# Schaltplan.net
KiCad netlist of a schematic drawn in EAGLE
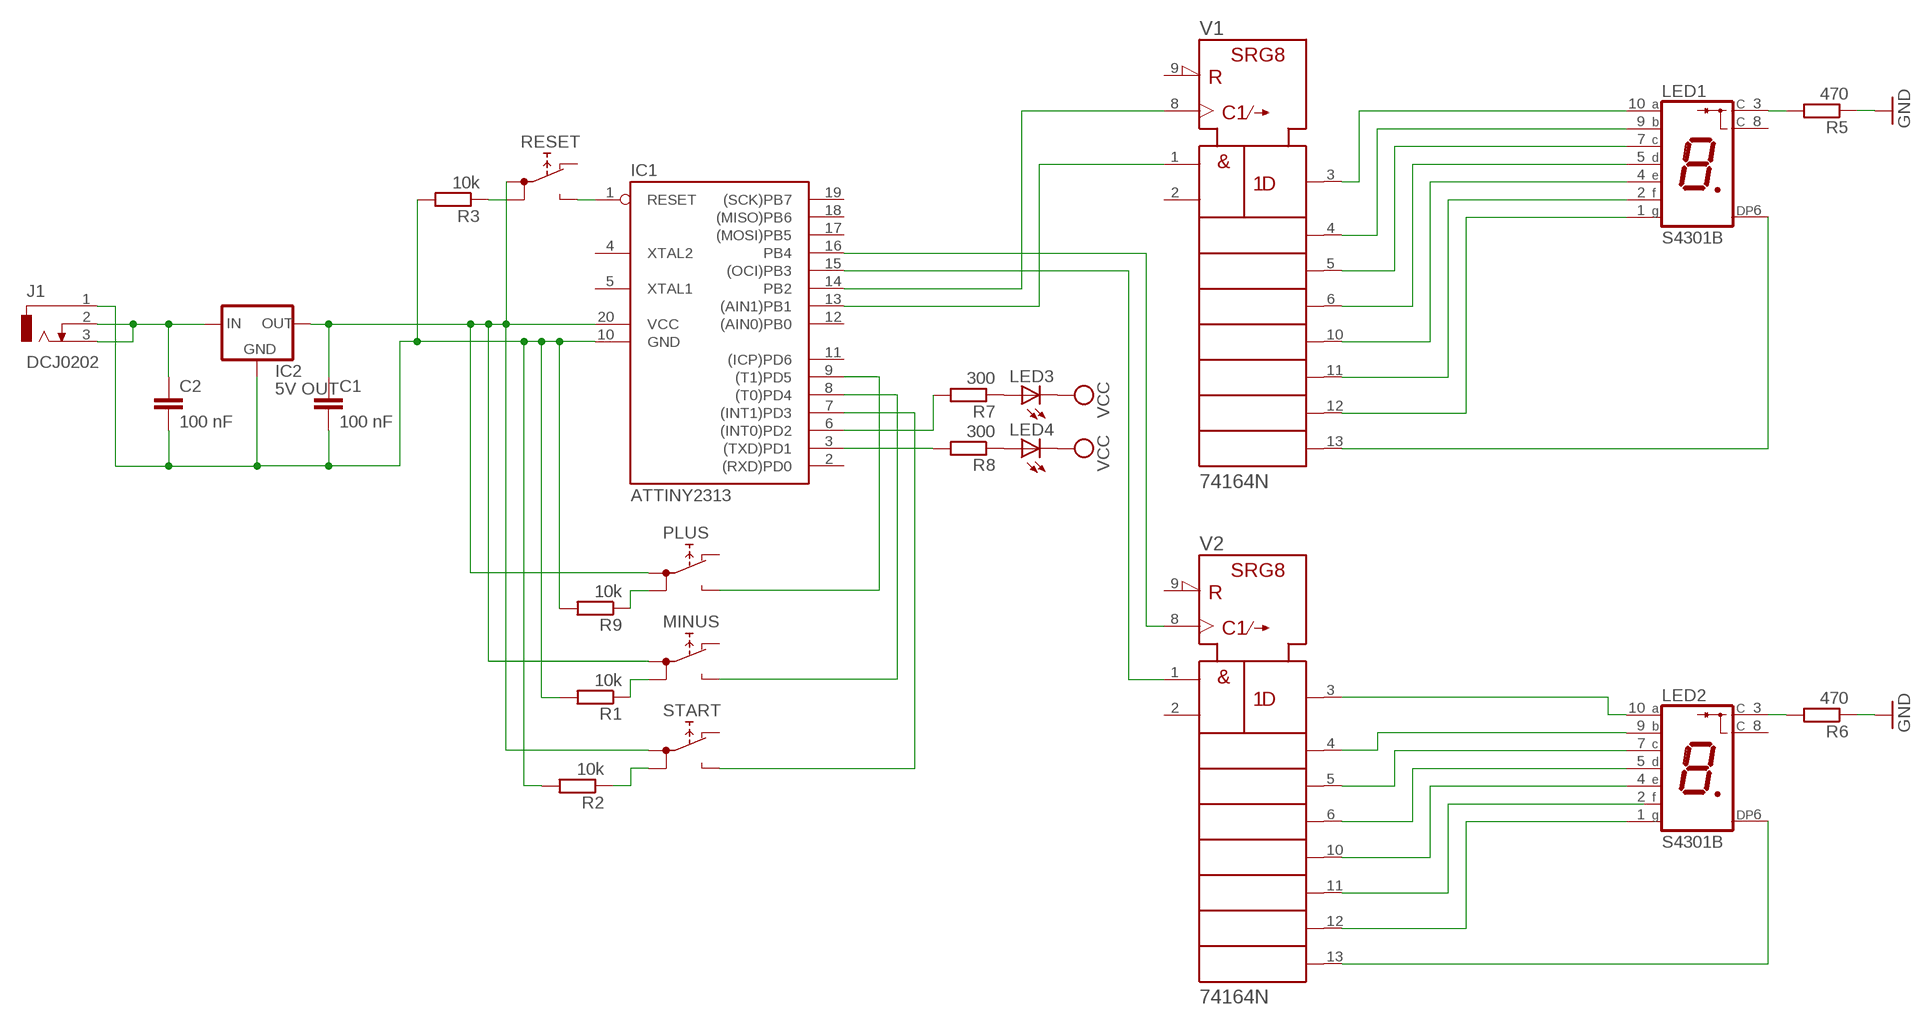
[diagram p0: schematic, sheet 1]

(export (version "E")
  (design (tool "Eeschema 10.0.6"))
  (components
    (comp (ref "C1")
      (value "100 nF")
      (footprint "eagle-import:C025-024X044")
      (libsource (lib "eagle-import") (part "C-EU025-024X044"))
    )
    (comp (ref "C2")
      (value "100 nF")
      (footprint "eagle-import:C025-024X044")
      (libsource (lib "eagle-import") (part "C-EU025-024X044"))
    )
    (comp (ref "IC1")
      (value "ATTINY2313")
      (footprint "eagle-import:DIL20")
      (libsource (lib "eagle-import") (part "AT90S2313P"))
    )
    (comp (ref "IC2")
      (value "5V OUT")
      (footprint "eagle-import:78MXXL")
      (libsource (lib "eagle-import") (part "78MXXL"))
    )
    (comp (ref "J1")
      (value "DCJ0202")
      (footprint "eagle-import:DCJ0202")
      (libsource (lib "eagle-import") (part "DCJ0202"))
    )
    (comp (ref "LED1")
      (value "S4301B")
      (footprint "eagle-import:S4301B")
      (libsource (lib "eagle-import") (part "S4301B"))
    )
    (comp (ref "LED2")
      (value "S4301B")
      (footprint "eagle-import:S4301B")
      (libsource (lib "eagle-import") (part "S4301B"))
    )
    (comp (ref "LED3")
      (value "LED3MM")
      (footprint "eagle-import:LED3MM")
      (libsource (lib "eagle-import") (part "LED3MM"))
    )
    (comp (ref "LED4")
      (value "LED3MM")
      (footprint "eagle-import:LED3MM")
      (libsource (lib "eagle-import") (part "LED3MM"))
    )
    (comp (ref "MINUS")
      (value "5501")
      (footprint "eagle-import:5501")
      (libsource (lib "eagle-import") (part "55?01"))
    )
    (comp (ref "PLUS")
      (value "5501")
      (footprint "eagle-import:5501")
      (libsource (lib "eagle-import") (part "55?01"))
    )
    (comp (ref "R1")
      (value "10k")
      (footprint "eagle-import:0204_7")
      (libsource (lib "eagle-import") (part "R-EU_0204/7"))
    )
    (comp (ref "R2")
      (value "10k")
      (footprint "eagle-import:0204_7")
      (libsource (lib "eagle-import") (part "R-EU_0204/7"))
    )
    (comp (ref "R3")
      (value "10k")
      (footprint "eagle-import:0204_7")
      (libsource (lib "eagle-import") (part "R-EU_0204/7"))
    )
    (comp (ref "R5")
      (value "470")
      (footprint "eagle-import:0204_7")
      (libsource (lib "eagle-import") (part "R-EU_0204/7"))
    )
    (comp (ref "R6")
      (value "470")
      (footprint "eagle-import:0204_7")
      (libsource (lib "eagle-import") (part "R-EU_0204/7"))
    )
    (comp (ref "R7")
      (value "300")
      (footprint "eagle-import:0204_7")
      (libsource (lib "eagle-import") (part "R-EU_0204/7"))
    )
    (comp (ref "R8")
      (value "300")
      (footprint "eagle-import:0204_7")
      (libsource (lib "eagle-import") (part "R-EU_0204/7"))
    )
    (comp (ref "R9")
      (value "10k")
      (footprint "eagle-import:0204_7")
      (libsource (lib "eagle-import") (part "R-EU_0204/7"))
    )
    (comp (ref "RESET")
      (value "5501")
      (footprint "eagle-import:5501")
      (libsource (lib "eagle-import") (part "55?01"))
    )
    (comp (ref "START")
      (value "5501")
      (footprint "eagle-import:5501")
      (libsource (lib "eagle-import") (part "55?01"))
    )
    (comp (ref "V1")
      (value "74164N")
      (footprint "eagle-import:DIL14")
      (libsource (lib "eagle-import") (part "74164N"))
    )
    (comp (ref "V2")
      (value "74164N")
      (footprint "eagle-import:DIL14")
      (libsource (lib "eagle-import") (part "74164N"))
    )
  )
  (nets
    (net (code "1") (name "GND") (class "Default")
      (node (ref "R5") (pin "1") (pinfunction "1_1") (pintype "passive"))
      (node (ref "R6") (pin "1") (pinfunction "1_1") (pintype "passive"))
    )
    (net (code "2") (name "Net-(C2-Pad1)") (class "Default")
      (node (ref "C2") (pin "1") (pinfunction "1_1") (pintype "passive"))
      (node (ref "IC2") (pin "IN") (pinfunction "IN_IN") (pintype "input"))
      (node (ref "J1") (pin "2") (pinfunction "2_2") (pintype "passive"))
      (node (ref "J1") (pin "3") (pinfunction "3_3") (pintype "passive"))
    )
    (net (code "3") (name "Net-(IC1-(AIN1)PB1)") (class "Default")
      (node (ref "IC1") (pin "13") (pinfunction "(AIN1)PB1_13") (pintype "bidirectional"))
      (node (ref "V1") (pin "1") (pinfunction "A_1") (pintype "input"))
    )
    (net (code "4") (name "Net-(IC1-(INT0)PD2)") (class "Default")
      (node (ref "IC1") (pin "6") (pinfunction "(INT0)PD2_6") (pintype "bidirectional"))
      (node (ref "R7") (pin "2") (pinfunction "2_2") (pintype "passive"))
    )
    (net (code "5") (name "Net-(IC1-(INT1)PD3)") (class "Default")
      (node (ref "IC1") (pin "7") (pinfunction "(INT1)PD3_7") (pintype "bidirectional"))
      (node (ref "START") (pin "NO") (pinfunction "NO_NO") (pintype "passive"))
    )
    (net (code "6") (name "Net-(IC1-(OCI)PB3)") (class "Default")
      (node (ref "IC1") (pin "15") (pinfunction "(OCI)PB3_15") (pintype "bidirectional"))
      (node (ref "V2") (pin "1") (pinfunction "A_1") (pintype "input"))
    )
    (net (code "7") (name "Net-(IC1-(T0)PD4)") (class "Default")
      (node (ref "IC1") (pin "8") (pinfunction "(T0)PD4_8") (pintype "bidirectional"))
      (node (ref "MINUS") (pin "NO") (pinfunction "NO_NO") (pintype "passive"))
    )
    (net (code "8") (name "Net-(IC1-(T1)PD5)") (class "Default")
      (node (ref "IC1") (pin "9") (pinfunction "(T1)PD5_9") (pintype "bidirectional"))
      (node (ref "PLUS") (pin "NO") (pinfunction "NO_NO") (pintype "passive"))
    )
    (net (code "9") (name "Net-(IC1-(TXD)PD1)") (class "Default")
      (node (ref "IC1") (pin "3") (pinfunction "(TXD)PD1_3") (pintype "bidirectional"))
      (node (ref "R8") (pin "2") (pinfunction "2_2") (pintype "passive"))
    )
    (net (code "10") (name "Net-(IC1-GND)") (class "Default")
      (node (ref "C1") (pin "2") (pinfunction "2_2") (pintype "passive"))
      (node (ref "C2") (pin "2") (pinfunction "2_2") (pintype "passive"))
      (node (ref "IC1") (pin "10") (pinfunction "GND_10") (pintype "power_in"))
      (node (ref "IC2") (pin "GND") (pinfunction "GND_GND") (pintype "input"))
      (node (ref "J1") (pin "1") (pinfunction "1_1") (pintype "passive"))
      (node (ref "R1") (pin "2") (pinfunction "2_2") (pintype "passive"))
      (node (ref "R2") (pin "2") (pinfunction "2_2") (pintype "passive"))
      (node (ref "R3") (pin "2") (pinfunction "2_2") (pintype "passive"))
      (node (ref "R9") (pin "2") (pinfunction "2_2") (pintype "passive"))
    )
    (net (code "11") (name "Net-(IC1-PB2)") (class "Default")
      (node (ref "IC1") (pin "14") (pinfunction "PB2_14") (pintype "bidirectional"))
      (node (ref "V1") (pin "8") (pinfunction "CLK_8") (pintype "input"))
    )
    (net (code "12") (name "Net-(IC1-PB4)") (class "Default")
      (node (ref "IC1") (pin "16") (pinfunction "PB4_16") (pintype "bidirectional"))
      (node (ref "V2") (pin "8") (pinfunction "CLK_8") (pintype "input"))
    )
    (net (code "13") (name "Net-(IC1-RESET)") (class "Default")
      (node (ref "IC1") (pin "1") (pinfunction "RESET_1") (pintype "bidirectional"))
      (node (ref "RESET") (pin "NO") (pinfunction "NO_NO") (pintype "passive"))
    )
    (net (code "14") (name "Net-(IC1-VCC)") (class "Default")
      (node (ref "C1") (pin "1") (pinfunction "1_1") (pintype "passive"))
      (node (ref "IC1") (pin "20") (pinfunction "VCC_20") (pintype "power_in"))
      (node (ref "IC2") (pin "OUT") (pinfunction "OUT_OUT") (pintype "passive"))
      (node (ref "MINUS") (pin "1A") (pinfunction "1A_1A") (pintype "passive"))
      (node (ref "PLUS") (pin "1A") (pinfunction "1A_1A") (pintype "passive"))
      (node (ref "RESET") (pin "1A") (pinfunction "1A_1A") (pintype "passive"))
      (node (ref "START") (pin "1A") (pinfunction "1A_1A") (pintype "passive"))
    )
    (net (code "15") (name "Net-(LED1-A)") (class "Default")
      (node (ref "LED1") (pin "10") (pinfunction "A_10") (pintype "passive"))
      (node (ref "V1") (pin "3") (pinfunction "QA_3") (pintype "output"))
    )
    (net (code "16") (name "Net-(LED1-B)") (class "Default")
      (node (ref "LED1") (pin "9") (pinfunction "B_9") (pintype "passive"))
      (node (ref "V1") (pin "4") (pinfunction "QB_4") (pintype "output"))
    )
    (net (code "17") (name "Net-(LED1-C-Pad3)") (class "Default")
      (node (ref "LED1") (pin "3") (pinfunction "C_3") (pintype "passive"))
      (node (ref "R5") (pin "2") (pinfunction "2_2") (pintype "passive"))
    )
    (net (code "18") (name "Net-(LED1-D)") (class "Default")
      (node (ref "LED1") (pin "5") (pinfunction "D_5") (pintype "passive"))
      (node (ref "V1") (pin "6") (pinfunction "QD_6") (pintype "output"))
    )
    (net (code "19") (name "Net-(LED1-DP)") (class "Default")
      (node (ref "LED1") (pin "6") (pinfunction "DP_6") (pintype "passive"))
      (node (ref "V1") (pin "13") (pinfunction "QH_13") (pintype "output"))
    )
    (net (code "20") (name "Net-(LED1-E)") (class "Default")
      (node (ref "LED1") (pin "4") (pinfunction "E_4") (pintype "passive"))
      (node (ref "V1") (pin "10") (pinfunction "QE_10") (pintype "output"))
    )
    (net (code "21") (name "Net-(LED1-F)") (class "Default")
      (node (ref "LED1") (pin "2") (pinfunction "F_2") (pintype "passive"))
      (node (ref "V1") (pin "11") (pinfunction "QF_11") (pintype "output"))
    )
    (net (code "22") (name "Net-(LED1-G)") (class "Default")
      (node (ref "LED1") (pin "1") (pinfunction "G_1") (pintype "passive"))
      (node (ref "V1") (pin "12") (pinfunction "QG_12") (pintype "output"))
    )
    (net (code "23") (name "Net-(LED2-A)") (class "Default")
      (node (ref "LED2") (pin "10") (pinfunction "A_10") (pintype "passive"))
      (node (ref "V2") (pin "3") (pinfunction "QA_3") (pintype "output"))
    )
    (net (code "24") (name "Net-(LED2-B)") (class "Default")
      (node (ref "LED2") (pin "9") (pinfunction "B_9") (pintype "passive"))
      (node (ref "V2") (pin "4") (pinfunction "QB_4") (pintype "output"))
    )
    (net (code "25") (name "Net-(LED2-C-Pad3)") (class "Default")
      (node (ref "LED2") (pin "3") (pinfunction "C_3") (pintype "passive"))
      (node (ref "R6") (pin "2") (pinfunction "2_2") (pintype "passive"))
    )
    (net (code "26") (name "Net-(LED2-D)") (class "Default")
      (node (ref "LED2") (pin "5") (pinfunction "D_5") (pintype "passive"))
      (node (ref "V2") (pin "6") (pinfunction "QD_6") (pintype "output"))
    )
    (net (code "27") (name "Net-(LED2-DP)") (class "Default")
      (node (ref "LED2") (pin "6") (pinfunction "DP_6") (pintype "passive"))
      (node (ref "V2") (pin "13") (pinfunction "QH_13") (pintype "output"))
    )
    (net (code "28") (name "Net-(LED2-E)") (class "Default")
      (node (ref "LED2") (pin "4") (pinfunction "E_4") (pintype "passive"))
      (node (ref "V2") (pin "10") (pinfunction "QE_10") (pintype "output"))
    )
    (net (code "29") (name "Net-(LED2-G)") (class "Default")
      (node (ref "LED2") (pin "1") (pinfunction "G_1") (pintype "passive"))
      (node (ref "V2") (pin "12") (pinfunction "QG_12") (pintype "output"))
    )
    (net (code "30") (name "Net-(LED3-PadA)") (class "Default")
      (node (ref "LED3") (pin "A") (pinfunction "A_A") (pintype "passive"))
      (node (ref "R7") (pin "1") (pinfunction "1_1") (pintype "passive"))
    )
    (net (code "31") (name "Net-(LED4-PadA)") (class "Default")
      (node (ref "LED4") (pin "A") (pinfunction "A_A") (pintype "passive"))
      (node (ref "R8") (pin "1") (pinfunction "1_1") (pintype "passive"))
    )
    (net (code "32") (name "Net-(MINUS-Pad1B)") (class "Default")
      (node (ref "MINUS") (pin "1B") (pinfunction "1B_1B") (pintype "passive"))
      (node (ref "R1") (pin "1") (pinfunction "1_1") (pintype "passive"))
    )
    (net (code "33") (name "Net-(PLUS-Pad1B)") (class "Default")
      (node (ref "PLUS") (pin "1B") (pinfunction "1B_1B") (pintype "passive"))
      (node (ref "R9") (pin "1") (pinfunction "1_1") (pintype "passive"))
    )
    (net (code "34") (name "Net-(R2-Pad1)") (class "Default")
      (node (ref "R2") (pin "1") (pinfunction "1_1") (pintype "passive"))
      (node (ref "START") (pin "1B") (pinfunction "1B_1B") (pintype "passive"))
    )
    (net (code "35") (name "Net-(R3-Pad1)") (class "Default")
      (node (ref "R3") (pin "1") (pinfunction "1_1") (pintype "passive"))
      (node (ref "RESET") (pin "1B") (pinfunction "1B_1B") (pintype "passive"))
    )
    (net (code "36") (name "Net-(V1C-QC)") (class "Default")
      (node (ref "LED1") (pin "7") (pinfunction "C_7") (pintype "passive"))
      (node (ref "V1") (pin "5") (pinfunction "QC_5") (pintype "output"))
    )
    (net (code "37") (name "Net-(V2C-QC)") (class "Default")
      (node (ref "LED2") (pin "7") (pinfunction "C_7") (pintype "passive"))
      (node (ref "V2") (pin "5") (pinfunction "QC_5") (pintype "output"))
    )
    (net (code "38") (name "VCC") (class "Default")
      (node (ref "LED3") (pin "K") (pinfunction "C_K") (pintype "passive"))
      (node (ref "LED4") (pin "K") (pinfunction "C_K") (pintype "passive"))
    )
    (net (code "39") (name "unconnected-(IC1-(AIN0)PB0-Pad12)") (class "Default")
      (node (ref "IC1") (pin "12") (pinfunction "(AIN0)PB0_12") (pintype "bidirectional"))
    )
    (net (code "40") (name "unconnected-(IC1-(ICP)PD6-Pad11)") (class "Default")
      (node (ref "IC1") (pin "11") (pinfunction "(ICP)PD6_11") (pintype "bidirectional"))
    )
    (net (code "41") (name "unconnected-(IC1-(MISO)PB6-Pad18)") (class "Default")
      (node (ref "IC1") (pin "18") (pinfunction "(MISO)PB6_18") (pintype "bidirectional"))
    )
    (net (code "42") (name "unconnected-(IC1-(MOSI)PB5-Pad17)") (class "Default")
      (node (ref "IC1") (pin "17") (pinfunction "(MOSI)PB5_17") (pintype "bidirectional"))
    )
    (net (code "43") (name "unconnected-(IC1-(RXD)PD0-Pad2)") (class "Default")
      (node (ref "IC1") (pin "2") (pinfunction "(RXD)PD0_2") (pintype "bidirectional"))
    )
    (net (code "44") (name "unconnected-(IC1-(SCK)PB7-Pad19)") (class "Default")
      (node (ref "IC1") (pin "19") (pinfunction "(SCK)PB7_19") (pintype "bidirectional"))
    )
    (net (code "45") (name "unconnected-(IC1-XTAL1-Pad5)") (class "Default")
      (node (ref "IC1") (pin "5") (pinfunction "XTAL1_5") (pintype "bidirectional"))
    )
    (net (code "46") (name "unconnected-(IC1-XTAL2-Pad4)") (class "Default")
      (node (ref "IC1") (pin "4") (pinfunction "XTAL2_4") (pintype "bidirectional"))
    )
    (net (code "47") (name "unconnected-(LED1-C-Pad8)") (class "Default")
      (node (ref "LED1") (pin "8") (pinfunction "C_8") (pintype "passive"))
    )
    (net (code "48") (name "unconnected-(LED2-C-Pad8)") (class "Default")
      (node (ref "LED2") (pin "8") (pinfunction "C_8") (pintype "passive"))
    )
    (net (code "49") (name "unconnected-(LED2-F-Pad2)") (class "Default")
      (node (ref "LED2") (pin "2") (pinfunction "F_2") (pintype "passive"))
    )
    (net (code "50") (name "unconnected-(MINUS-PadNC)") (class "Default")
      (node (ref "MINUS") (pin "NC") (pinfunction "NC_NC") (pintype "passive"))
    )
    (net (code "51") (name "unconnected-(PLUS-PadNC)") (class "Default")
      (node (ref "PLUS") (pin "NC") (pinfunction "NC_NC") (pintype "passive"))
    )
    (net (code "52") (name "unconnected-(RESET-PadNC)") (class "Default")
      (node (ref "RESET") (pin "NC") (pinfunction "NC_NC") (pintype "passive"))
    )
    (net (code "53") (name "unconnected-(START-PadNC)") (class "Default")
      (node (ref "START") (pin "NC") (pinfunction "NC_NC") (pintype "passive"))
    )
    (net (code "54") (name "unconnected-(V1C-B-Pad2)") (class "Default")
      (node (ref "V1") (pin "2") (pinfunction "B_2") (pintype "input"))
    )
    (net (code "55") (name "unconnected-(V1C-~{CLR}-Pad9)") (class "Default")
      (node (ref "V1") (pin "9") (pinfunction "~{CLR}_9") (pintype "input"))
    )
    (net (code "56") (name "unconnected-(V2C-B-Pad2)") (class "Default")
      (node (ref "V2") (pin "2") (pinfunction "B_2") (pintype "input"))
    )
    (net (code "57") (name "unconnected-(V2C-QF-Pad11)") (class "Default")
      (node (ref "V2") (pin "11") (pinfunction "QF_11") (pintype "output"))
    )
    (net (code "58") (name "unconnected-(V2C-~{CLR}-Pad9)") (class "Default")
      (node (ref "V2") (pin "9") (pinfunction "~{CLR}_9") (pintype "input"))
    )
  )
)
